# Sheet2.net
KiCad netlist of a schematic drawn in Altium Designer
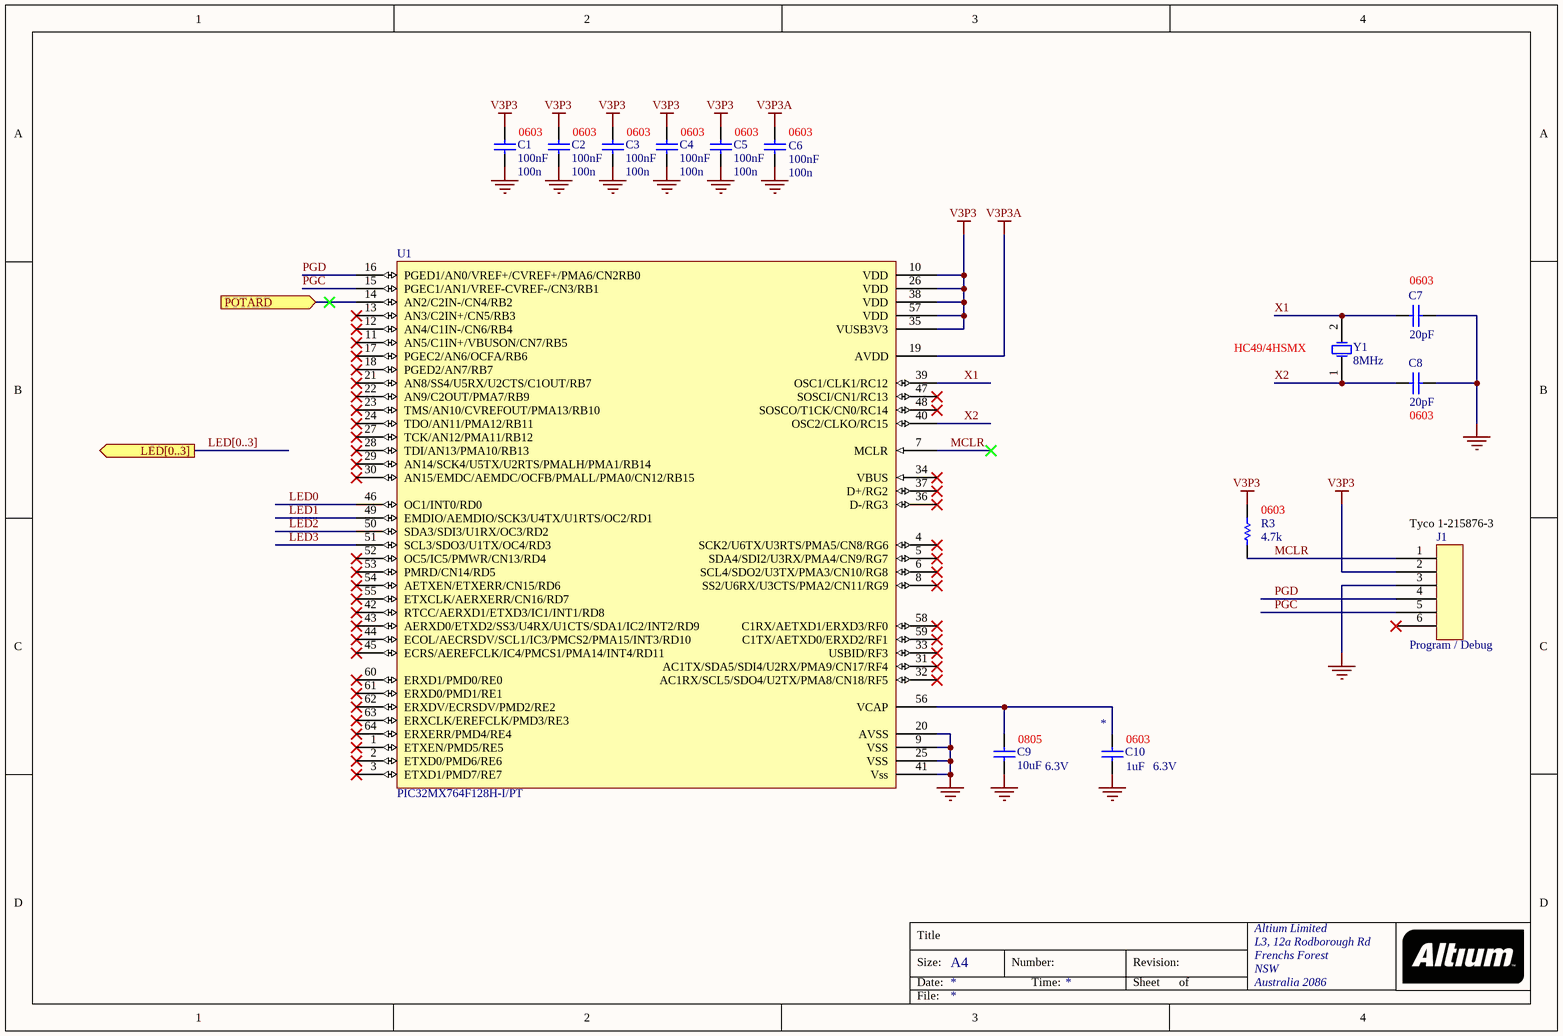
[diagram p0: Sheet2.SchDoc]

(export (version "E")
  (design (tool "Eeschema 10.0.6"))
  (components
    (comp (ref "C1")
      (value "100n")
      (footprint "CAPC1608N")
      (description "Capacitor")
      (fields (field (name "ALTIUM_VALUE") "100nF") (field (name "PUBLISHER") "Altium Limited"))
      (libsource (lib "Miscellaneous Devices") (part "Cap"))
    )
    (comp (ref "C2")
      (value "100n")
      (footprint "CAPC1608N")
      (description "Capacitor")
      (fields (field (name "ALTIUM_VALUE") "100nF") (field (name "PUBLISHER") "Altium Limited"))
      (libsource (lib "Miscellaneous Devices") (part "Cap"))
    )
    (comp (ref "C3")
      (value "100n")
      (footprint "CAPC1608N")
      (description "Capacitor")
      (fields (field (name "ALTIUM_VALUE") "100nF") (field (name "PUBLISHER") "Altium Limited"))
      (libsource (lib "Miscellaneous Devices") (part "Cap"))
    )
    (comp (ref "C4")
      (value "100n")
      (footprint "CAPC1608N")
      (description "Capacitor")
      (fields (field (name "ALTIUM_VALUE") "100nF") (field (name "PUBLISHER") "Altium Limited"))
      (libsource (lib "Miscellaneous Devices") (part "Cap"))
    )
    (comp (ref "C5")
      (value "100n")
      (footprint "CAPC1608N")
      (description "Capacitor")
      (fields (field (name "ALTIUM_VALUE") "100nF") (field (name "PUBLISHER") "Altium Limited"))
      (libsource (lib "Miscellaneous Devices") (part "Cap"))
    )
    (comp (ref "C6")
      (value "100n")
      (footprint "CAPC1608N")
      (description "Capacitor")
      (fields (field (name "ALTIUM_VALUE") "100nF") (field (name "PUBLISHER") "Altium Limited"))
      (libsource (lib "Miscellaneous Devices") (part "Cap"))
    )
    (comp (ref "C7")
      (value "20pF")
      (footprint "CAPC1608N")
      (description "Capacitor")
      (fields (field (name "Comment") "20p") (field (name "PUBLISHER") "Altium Limited"))
      (libsource (lib "Miscellaneous Devices") (part "Cap"))
    )
    (comp (ref "C8")
      (value "20pF")
      (footprint "CAPC1608N")
      (description "Capacitor")
      (fields (field (name "Comment") "20p") (field (name "PUBLISHER") "Altium Limited"))
      (libsource (lib "Miscellaneous Devices") (part "Cap"))
    )
    (comp (ref "C9")
      (value "6.3V")
      (footprint "CAPC2012N")
      (description "Capacitor")
      (fields (field (name "ALTIUM_VALUE") "10uF") (field (name "PUBLISHER") "Altium Limited"))
      (libsource (lib "Miscellaneous Devices") (part "Cap"))
    )
    (comp (ref "C10")
      (value "6.3V")
      (footprint "CAPC1608N")
      (description "Capacitor")
      (fields
        (field (name "ALTIUM_VALUE") "1uF")
        (field (name "FABRICANT") "*")
        (field (name "PUBLISHER") "Altium Limited")
      )
      (libsource (lib "Miscellaneous Devices") (part "Cap"))
    )
    (comp (ref "J1")
      (value "Program / Debug")
      (footprint "RJ12_90")
      (libsource (lib "SchDebug") (part "Component_1"))
    )
    (comp (ref "R3")
      (value "4.7k")
      (footprint "RESC1608N")
      (description "Resistor")
      (fields (field (name "Comment") "Res1") (field (name "PUBLISHER") "Altium Limited"))
      (libsource (lib "Miscellaneous Devices") (part "Res1"))
    )
    (comp (ref "U1")
      (value "PIC32MX764F128H-I/PT")
      (footprint "QFP50P1200X1200X120-64")
      (libsource (lib "SchDebug") (part "PIC 32"))
    )
    (comp (ref "Y1")
      (value "8MHz")
      (footprint "HC49/4H SMX CRYSTAL")
      (description "Crystal Oscillator")
      (fields (field (name "PUBLISHER") "Altium Limited"))
      (libsource (lib "Miscellaneous Devices") (part "XTAL"))
    )
  )
  (nets
    (net (code "1") (name "/LED0") (class "Default")
      (node (ref "U1") (pin "46") (pinfunction "OC1/INT0/RD0_46") (pintype "bidirectional"))
    )
    (net (code "2") (name "/LED1") (class "Default")
      (node (ref "U1") (pin "49") (pinfunction "EMDIO/AEMDIO/SCK3/U4TX/U1RTS/OC2/RD1_49") (pintype "bidirectional"))
    )
    (net (code "3") (name "/LED2") (class "Default")
      (node (ref "U1") (pin "50") (pinfunction "SDA3/SDI3/U1RX/OC3/RD2_50") (pintype "bidirectional"))
    )
    (net (code "4") (name "/LED3") (class "Default")
      (node (ref "U1") (pin "51") (pinfunction "SCL3/SDO3/U1TX/OC4/RD3_51") (pintype "bidirectional"))
    )
    (net (code "6") (name "/MCLR") (class "Default")
      (node (ref "J1") (pin "1") (pinfunction "1_1") (pintype "passive"))
      (node (ref "R3") (pin "1") (pinfunction "1_1") (pintype "passive"))
      (node (ref "U1") (pin "7") (pinfunction "MCLR_7") (pintype "input"))
    )
    (net (code "7") (name "/PGC") (class "Default")
      (node (ref "J1") (pin "5") (pinfunction "5_5") (pintype "passive"))
      (node (ref "U1") (pin "15") (pinfunction "PGEC1/AN1/VREF-CVREF-/CN3/RB1_15") (pintype "bidirectional"))
    )
    (net (code "8") (name "/PGD") (class "Default")
      (node (ref "J1") (pin "4") (pinfunction "4_4") (pintype "passive"))
      (node (ref "U1") (pin "16") (pinfunction "PGED1/AN0/VREF+/CVREF+/PMA6/CN2RB0_16") (pintype "bidirectional"))
    )
    (net (code "9") (name "/POTARD") (class "Default")
      (node (ref "U1") (pin "14") (pinfunction "AN2/C2IN-/CN4/RB2_14") (pintype "bidirectional+no_connect"))
    )
    (net (code "10") (name "/X1") (class "Default")
      (node (ref "C7") (pin "1") (pinfunction "1_1") (pintype "passive"))
      (node (ref "U1") (pin "39") (pinfunction "OSC1/CLK1/RC12_39") (pintype "bidirectional"))
      (node (ref "Y1") (pin "2") (pinfunction "OSC2_2") (pintype "passive"))
    )
    (net (code "11") (name "/X2") (class "Default")
      (node (ref "C8") (pin "1") (pinfunction "1_1") (pintype "passive"))
      (node (ref "U1") (pin "40") (pinfunction "OSC2/CLKO/RC15_40") (pintype "bidirectional"))
      (node (ref "Y1") (pin "1") (pinfunction "OSC1_1") (pintype "passive"))
    )
    (net (code "12") (name "GND") (class "Default")
      (node (ref "C1") (pin "1") (pinfunction "1_1") (pintype "passive"))
      (node (ref "C10") (pin "2") (pinfunction "2_2") (pintype "passive"))
      (node (ref "C2") (pin "1") (pinfunction "1_1") (pintype "passive"))
      (node (ref "C3") (pin "1") (pinfunction "1_1") (pintype "passive"))
      (node (ref "C4") (pin "1") (pinfunction "1_1") (pintype "passive"))
      (node (ref "C5") (pin "1") (pinfunction "1_1") (pintype "passive"))
      (node (ref "C6") (pin "1") (pinfunction "1_1") (pintype "passive"))
      (node (ref "C7") (pin "2") (pinfunction "2_2") (pintype "passive"))
      (node (ref "C8") (pin "2") (pinfunction "2_2") (pintype "passive"))
      (node (ref "C9") (pin "2") (pinfunction "2_2") (pintype "passive"))
      (node (ref "J1") (pin "3") (pinfunction "3_3") (pintype "passive"))
      (node (ref "U1") (pin "20") (pinfunction "AVSS_20") (pintype "passive"))
      (node (ref "U1") (pin "25") (pinfunction "VSS_25") (pintype "passive"))
      (node (ref "U1") (pin "41") (pinfunction "Vss_41") (pintype "passive"))
      (node (ref "U1") (pin "9") (pinfunction "VSS_9") (pintype "passive"))
    )
    (net (code "13") (name "Net-(U1-VCAP)") (class "Default")
      (node (ref "C10") (pin "1") (pinfunction "1_1") (pintype "passive"))
      (node (ref "C9") (pin "1") (pinfunction "1_1") (pintype "passive"))
      (node (ref "U1") (pin "56") (pinfunction "VCAP_56") (pintype "passive"))
    )
    (net (code "14") (name "V3P3") (class "Default")
      (node (ref "C1") (pin "2") (pinfunction "2_2") (pintype "passive"))
      (node (ref "C2") (pin "2") (pinfunction "2_2") (pintype "passive"))
      (node (ref "C3") (pin "2") (pinfunction "2_2") (pintype "passive"))
      (node (ref "C4") (pin "2") (pinfunction "2_2") (pintype "passive"))
      (node (ref "C5") (pin "2") (pinfunction "2_2") (pintype "passive"))
      (node (ref "J1") (pin "2") (pinfunction "2_2") (pintype "passive"))
      (node (ref "R3") (pin "2") (pinfunction "2_2") (pintype "passive"))
      (node (ref "U1") (pin "10") (pinfunction "VDD_10") (pintype "passive"))
      (node (ref "U1") (pin "26") (pinfunction "VDD_26") (pintype "passive"))
      (node (ref "U1") (pin "35") (pinfunction "VUSB3V3_35") (pintype "passive"))
      (node (ref "U1") (pin "38") (pinfunction "VDD_38") (pintype "passive"))
      (node (ref "U1") (pin "57") (pinfunction "VDD_57") (pintype "passive"))
    )
    (net (code "15") (name "V3P3A") (class "Default")
      (node (ref "C6") (pin "2") (pinfunction "2_2") (pintype "passive"))
      (node (ref "U1") (pin "19") (pinfunction "AVDD_19") (pintype "passive"))
    )
    (net (code "16") (name "unconnected-(J1-Pad6)") (class "Default")
      (node (ref "J1") (pin "6") (pinfunction "6_6") (pintype "passive+no_connect"))
    )
    (net (code "17") (name "unconnected-(U1-AC1RX{slash}SCL5{slash}SDO4{slash}U2TX{slash}PMA8{slash}CN18{slash}RF5-Pad32)") (class "Default")
      (node (ref "U1") (pin "32") (pinfunction "AC1RX/SCL5/SDO4/U2TX/PMA8/CN18/RF5_32") (pintype "bidirectional+no_connect"))
    )
    (net (code "18") (name "unconnected-(U1-AC1TX{slash}SDA5{slash}SDI4{slash}U2RX{slash}PMA9{slash}CN17{slash}RF4-Pad31)") (class "Default")
      (node (ref "U1") (pin "31") (pinfunction "AC1TX/SDA5/SDI4/U2RX/PMA9/CN17/RF4_31") (pintype "bidirectional+no_connect"))
    )
    (net (code "19") (name "unconnected-(U1-AERXD0{slash}ETXD2{slash}SS3{slash}U4RX{slash}U1CTS{slash}SDA1{slash}IC2{slash}INT2{slash}RD9-Pad43)") (class "Default")
      (node (ref "U1") (pin "43") (pinfunction "AERXD0/ETXD2/SS3/U4RX/U1CTS/SDA1/IC2/INT2/RD9_43") (pintype "bidirectional+no_connect"))
    )
    (net (code "20") (name "unconnected-(U1-AETXEN{slash}ETXERR{slash}CN15{slash}RD6-Pad54)") (class "Default")
      (node (ref "U1") (pin "54") (pinfunction "AETXEN/ETXERR/CN15/RD6_54") (pintype "bidirectional+no_connect"))
    )
    (net (code "21") (name "unconnected-(U1-AN3{slash}C2IN+{slash}CN5{slash}RB3-Pad13)") (class "Default")
      (node (ref "U1") (pin "13") (pinfunction "AN3/C2IN+/CN5/RB3_13") (pintype "bidirectional+no_connect"))
    )
    (net (code "22") (name "unconnected-(U1-AN4{slash}C1IN-{slash}CN6{slash}RB4-Pad12)") (class "Default")
      (node (ref "U1") (pin "12") (pinfunction "AN4/C1IN-/CN6/RB4_12") (pintype "bidirectional+no_connect"))
    )
    (net (code "23") (name "unconnected-(U1-AN5{slash}C1IN+{slash}VBUSON{slash}CN7{slash}RB5-Pad11)") (class "Default")
      (node (ref "U1") (pin "11") (pinfunction "AN5/C1IN+/VBUSON/CN7/RB5_11") (pintype "bidirectional+no_connect"))
    )
    (net (code "24") (name "unconnected-(U1-AN8{slash}SS4{slash}U5RX{slash}U2CTS{slash}C1OUT{slash}RB7-Pad21)") (class "Default")
      (node (ref "U1") (pin "21") (pinfunction "AN8/SS4/U5RX/U2CTS/C1OUT/RB7_21") (pintype "bidirectional+no_connect"))
    )
    (net (code "25") (name "unconnected-(U1-AN9{slash}C2OUT{slash}PMA7{slash}RB9-Pad22)") (class "Default")
      (node (ref "U1") (pin "22") (pinfunction "AN9/C2OUT/PMA7/RB9_22") (pintype "bidirectional+no_connect"))
    )
    (net (code "26") (name "unconnected-(U1-AN14{slash}SCK4{slash}U5TX{slash}U2RTS{slash}PMALH{slash}PMA1{slash}RB14-Pad29)") (class "Default")
      (node (ref "U1") (pin "29") (pinfunction "AN14/SCK4/U5TX/U2RTS/PMALH/PMA1/RB14_29") (pintype "bidirectional+no_connect"))
    )
    (net (code "27") (name "unconnected-(U1-AN15{slash}EMDC{slash}AEMDC{slash}OCFB{slash}PMALL{slash}PMA0{slash}CN12{slash}RB15-Pad30)") (class "Default")
      (node (ref "U1") (pin "30") (pinfunction "AN15/EMDC/AEMDC/OCFB/PMALL/PMA0/CN12/RB15_30") (pintype "bidirectional+no_connect"))
    )
    (net (code "28") (name "unconnected-(U1-C1RX{slash}AETXD1{slash}ERXD3{slash}RF0-Pad58)") (class "Default")
      (node (ref "U1") (pin "58") (pinfunction "C1RX/AETXD1/ERXD3/RF0_58") (pintype "bidirectional+no_connect"))
    )
    (net (code "29") (name "unconnected-(U1-C1TX{slash}AETXD0{slash}ERXD2{slash}RF1-Pad59)") (class "Default")
      (node (ref "U1") (pin "59") (pinfunction "C1TX/AETXD0/ERXD2/RF1_59") (pintype "bidirectional+no_connect"))
    )
    (net (code "30") (name "unconnected-(U1-D+{slash}RG2-Pad37)") (class "Default")
      (node (ref "U1") (pin "37") (pinfunction "D+/RG2_37") (pintype "bidirectional+no_connect"))
    )
    (net (code "31") (name "unconnected-(U1-D-{slash}RG3-Pad36)") (class "Default")
      (node (ref "U1") (pin "36") (pinfunction "D-/RG3_36") (pintype "bidirectional+no_connect"))
    )
    (net (code "32") (name "unconnected-(U1-ECOL{slash}AECRSDV{slash}SCL1{slash}IC3{slash}PMCS2{slash}PMA15{slash}INT3{slash}RD10-Pad44)") (class "Default")
      (node (ref "U1") (pin "44") (pinfunction "ECOL/AECRSDV/SCL1/IC3/PMCS2/PMA15/INT3/RD10_44") (pintype "bidirectional+no_connect"))
    )
    (net (code "33") (name "unconnected-(U1-ECRS{slash}AEREFCLK{slash}IC4{slash}PMCS1{slash}PMA14{slash}INT4{slash}RD11-Pad45)") (class "Default")
      (node (ref "U1") (pin "45") (pinfunction "ECRS/AEREFCLK/IC4/PMCS1/PMA14/INT4/RD11_45") (pintype "bidirectional+no_connect"))
    )
    (net (code "34") (name "unconnected-(U1-ERXCLK{slash}EREFCLK{slash}PMD3{slash}RE3-Pad63)") (class "Default")
      (node (ref "U1") (pin "63") (pinfunction "ERXCLK/EREFCLK/PMD3/RE3_63") (pintype "bidirectional+no_connect"))
    )
    (net (code "35") (name "unconnected-(U1-ERXD0{slash}PMD1{slash}RE1-Pad61)") (class "Default")
      (node (ref "U1") (pin "61") (pinfunction "ERXD0/PMD1/RE1_61") (pintype "bidirectional+no_connect"))
    )
    (net (code "36") (name "unconnected-(U1-ERXD1{slash}PMD0{slash}RE0-Pad60)") (class "Default")
      (node (ref "U1") (pin "60") (pinfunction "ERXD1/PMD0/RE0_60") (pintype "bidirectional+no_connect"))
    )
    (net (code "37") (name "unconnected-(U1-ERXDV{slash}ECRSDV{slash}PMD2{slash}RE2-Pad62)") (class "Default")
      (node (ref "U1") (pin "62") (pinfunction "ERXDV/ECRSDV/PMD2/RE2_62") (pintype "bidirectional+no_connect"))
    )
    (net (code "38") (name "unconnected-(U1-ERXERR{slash}PMD4{slash}RE4-Pad64)") (class "Default")
      (node (ref "U1") (pin "64") (pinfunction "ERXERR/PMD4/RE4_64") (pintype "bidirectional+no_connect"))
    )
    (net (code "39") (name "unconnected-(U1-ETXCLK{slash}AERXERR{slash}CN16{slash}RD7-Pad55)") (class "Default")
      (node (ref "U1") (pin "55") (pinfunction "ETXCLK/AERXERR/CN16/RD7_55") (pintype "bidirectional+no_connect"))
    )
    (net (code "40") (name "unconnected-(U1-ETXD0{slash}PMD6{slash}RE6-Pad2)") (class "Default")
      (node (ref "U1") (pin "2") (pinfunction "ETXD0/PMD6/RE6_2") (pintype "bidirectional+no_connect"))
    )
    (net (code "41") (name "unconnected-(U1-ETXD1{slash}PMD7{slash}RE7-Pad3)") (class "Default")
      (node (ref "U1") (pin "3") (pinfunction "ETXD1/PMD7/RE7_3") (pintype "bidirectional+no_connect"))
    )
    (net (code "42") (name "unconnected-(U1-ETXEN{slash}PMD5{slash}RE5-Pad1)") (class "Default")
      (node (ref "U1") (pin "1") (pinfunction "ETXEN/PMD5/RE5_1") (pintype "bidirectional+no_connect"))
    )
    (net (code "43") (name "unconnected-(U1-OC5{slash}IC5{slash}PMWR{slash}CN13{slash}RD4-Pad52)") (class "Default")
      (node (ref "U1") (pin "52") (pinfunction "OC5/IC5/PMWR/CN13/RD4_52") (pintype "bidirectional+no_connect"))
    )
    (net (code "44") (name "unconnected-(U1-PGEC2{slash}AN6{slash}OCFA{slash}RB6-Pad17)") (class "Default")
      (node (ref "U1") (pin "17") (pinfunction "PGEC2/AN6/OCFA/RB6_17") (pintype "bidirectional+no_connect"))
    )
    (net (code "45") (name "unconnected-(U1-PGED2{slash}AN7{slash}RB7-Pad18)") (class "Default")
      (node (ref "U1") (pin "18") (pinfunction "PGED2/AN7/RB7_18") (pintype "bidirectional+no_connect"))
    )
    (net (code "46") (name "unconnected-(U1-PMRD{slash}CN14{slash}RD5-Pad53)") (class "Default")
      (node (ref "U1") (pin "53") (pinfunction "PMRD/CN14/RD5_53") (pintype "bidirectional+no_connect"))
    )
    (net (code "47") (name "unconnected-(U1-RTCC{slash}AERXD1{slash}ETXD3{slash}IC1{slash}INT1{slash}RD8-Pad42)") (class "Default")
      (node (ref "U1") (pin "42") (pinfunction "RTCC/AERXD1/ETXD3/IC1/INT1/RD8_42") (pintype "bidirectional+no_connect"))
    )
    (net (code "48") (name "unconnected-(U1-SCK2{slash}U6TX{slash}U3RTS{slash}PMA5{slash}CN8{slash}RG6-Pad4)") (class "Default")
      (node (ref "U1") (pin "4") (pinfunction "SCK2/U6TX/U3RTS/PMA5/CN8/RG6_4") (pintype "bidirectional+no_connect"))
    )
    (net (code "49") (name "unconnected-(U1-SCL4{slash}SDO2{slash}U3TX{slash}PMA3{slash}CN10{slash}RG8-Pad6)") (class "Default")
      (node (ref "U1") (pin "6") (pinfunction "SCL4/SDO2/U3TX/PMA3/CN10/RG8_6") (pintype "bidirectional+no_connect"))
    )
    (net (code "50") (name "unconnected-(U1-SDA4{slash}SDI2{slash}U3RX{slash}PMA4{slash}CN9{slash}RG7-Pad5)") (class "Default")
      (node (ref "U1") (pin "5") (pinfunction "SDA4/SDI2/U3RX/PMA4/CN9/RG7_5") (pintype "bidirectional+no_connect"))
    )
    (net (code "51") (name "unconnected-(U1-SOSCI{slash}CN1{slash}RC13-Pad47)") (class "Default")
      (node (ref "U1") (pin "47") (pinfunction "SOSCI/CN1/RC13_47") (pintype "bidirectional+no_connect"))
    )
    (net (code "52") (name "unconnected-(U1-SOSCO{slash}T1CK{slash}CN0{slash}RC14-Pad48)") (class "Default")
      (node (ref "U1") (pin "48") (pinfunction "SOSCO/T1CK/CN0/RC14_48") (pintype "bidirectional+no_connect"))
    )
    (net (code "53") (name "unconnected-(U1-SS2{slash}U6RX{slash}U3CTS{slash}PMA2{slash}CN11{slash}RG9-Pad8)") (class "Default")
      (node (ref "U1") (pin "8") (pinfunction "SS2/U6RX/U3CTS/PMA2/CN11/RG9_8") (pintype "bidirectional+no_connect"))
    )
    (net (code "54") (name "unconnected-(U1-TCK{slash}AN12{slash}PMA11{slash}RB12-Pad27)") (class "Default")
      (node (ref "U1") (pin "27") (pinfunction "TCK/AN12/PMA11/RB12_27") (pintype "bidirectional+no_connect"))
    )
    (net (code "55") (name "unconnected-(U1-TDI{slash}AN13{slash}PMA10{slash}RB13-Pad28)") (class "Default")
      (node (ref "U1") (pin "28") (pinfunction "TDI/AN13/PMA10/RB13_28") (pintype "bidirectional+no_connect"))
    )
    (net (code "56") (name "unconnected-(U1-TDO{slash}AN11{slash}PMA12{slash}RB11-Pad24)") (class "Default")
      (node (ref "U1") (pin "24") (pinfunction "TDO/AN11/PMA12/RB11_24") (pintype "bidirectional+no_connect"))
    )
    (net (code "57") (name "unconnected-(U1-TMS{slash}AN10{slash}CVREFOUT{slash}PMA13{slash}RB10-Pad23)") (class "Default")
      (node (ref "U1") (pin "23") (pinfunction "TMS/AN10/CVREFOUT/PMA13/RB10_23") (pintype "bidirectional+no_connect"))
    )
    (net (code "58") (name "unconnected-(U1-USBID{slash}RF3-Pad33)") (class "Default")
      (node (ref "U1") (pin "33") (pinfunction "USBID/RF3_33") (pintype "bidirectional+no_connect"))
    )
    (net (code "59") (name "unconnected-(U1-VBUS-Pad34)") (class "Default")
      (node (ref "U1") (pin "34") (pinfunction "VBUS_34") (pintype "input+no_connect"))
    )
  )
)
